# SCH_BMS.net
KiCad netlist of a schematic drawn in Altium Designer
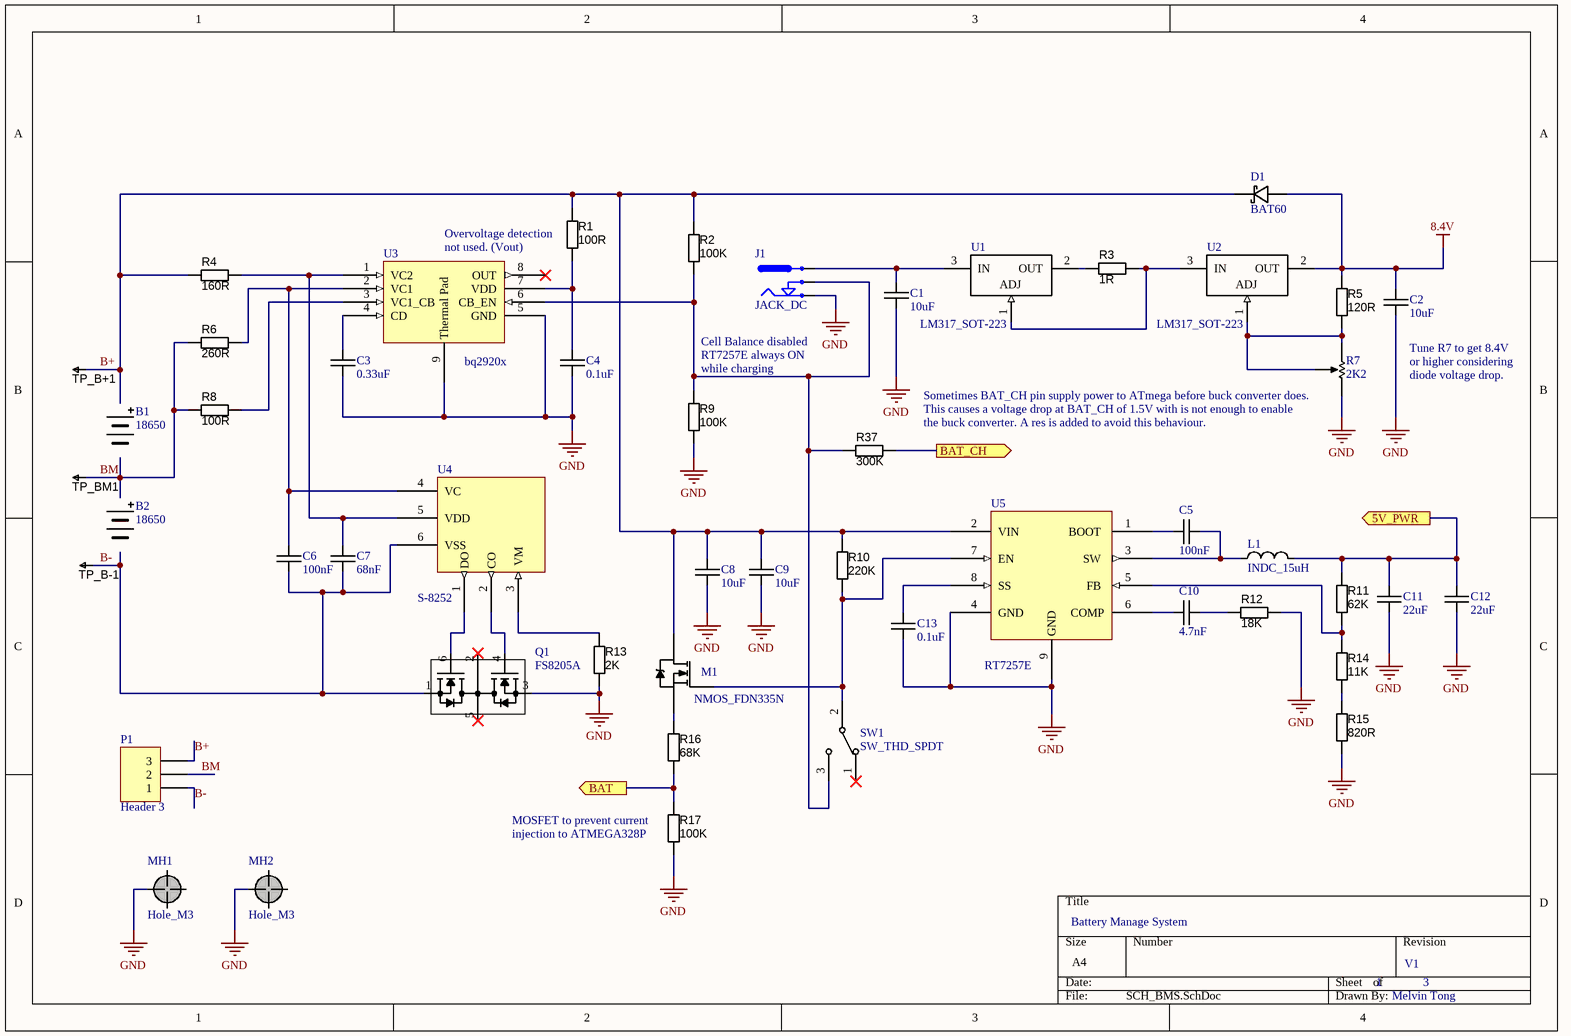
[diagram p0: SCH_BMS.SchDoc]

(export (version "E")
  (design (tool "Eeschema 10.0.6"))
  (components
    (comp (ref "B1") (value "18650") (libsource (lib "Schlib_Sword") (part "Battery_18650")))
    (comp (ref "B2") (value "18650") (libsource (lib "Schlib_Sword") (part "Battery_18650")))
    (comp (ref "C1")
      (value "10uF")
      (footprint "CAP_0805")
      (description "SMD 0805/1206")
      (libsource (lib "Schlib_Sword") (part "CAP_10uF"))
    )
    (comp (ref "C2")
      (value "10uF")
      (footprint "CAP_1206")
      (description "SMD 0805/1206")
      (libsource (lib "Schlib_Sword") (part "CAP_10uF"))
    )
    (comp (ref "C3")
      (value "0.33uF")
      (footprint "CAP_0805")
      (description "SMD 0805")
      (libsource (lib "Schlib_Sword") (part "CAP_330nF"))
    )
    (comp (ref "C4")
      (value "0.1uF")
      (footprint "CAP_0805")
      (description "SMD 0805")
      (libsource (lib "Schlib_Sword") (part "CAP_0.1uF"))
    )
    (comp (ref "C5")
      (value "100nF")
      (footprint "CAP_0805")
      (description "SMD 0805")
      (libsource (lib "Schlib_Sword") (part "CAP_100nF"))
    )
    (comp (ref "C6")
      (value "100nF")
      (footprint "CAP_0805")
      (description "SMD 0805")
      (libsource (lib "Schlib_Sword") (part "CAP_0.1uF"))
    )
    (comp (ref "C7")
      (value "68nF")
      (footprint "CAP_0805")
      (description "SMD 0805")
      (libsource (lib "Schlib_Sword") (part "CAP_0.1uF"))
    )
    (comp (ref "C8")
      (value "10uF")
      (footprint "CAP_1206")
      (description "SMD 0805/1206")
      (libsource (lib "Schlib_Sword") (part "CAP_10uF"))
    )
    (comp (ref "C9")
      (value "10uF")
      (footprint "CAP_1206")
      (description "SMD 0805/1206")
      (libsource (lib "Schlib_Sword") (part "CAP_10uF"))
    )
    (comp (ref "C10")
      (value "4.7nF")
      (footprint "CAP_0805")
      (description "SMD 0805")
      (libsource (lib "Schlib_Sword") (part "CAP_4.7nF"))
    )
    (comp (ref "C11")
      (value "22uF")
      (footprint "CAP_1206")
      (description "SMD 1206")
      (libsource (lib "Schlib_Sword") (part "CAP_22uF"))
    )
    (comp (ref "C12")
      (value "22uF")
      (footprint "CAP_1206")
      (description "SMD 1206")
      (libsource (lib "Schlib_Sword") (part "CAP_22uF"))
    )
    (comp (ref "C13")
      (value "0.1uF")
      (footprint "CAP_0805")
      (description "SMD 0805")
      (libsource (lib "Schlib_Sword") (part "CAP_0.1uF"))
    )
    (comp (ref "D1")
      (value "BAT60")
      (footprint "SOD323")
      (description "Schottky Diode 3A, Vf~0.24V, Vr=10V")
      (libsource (lib "Schlib_Sword") (part "BAT60"))
    )
    (comp (ref "J1") (value "JACK_DC") (footprint "DC-004") (libsource (lib "Schlib_Sword") (part "JACK_DC")))
    (comp (ref "L1")
      (value "INDC_15uH")
      (footprint "IND_15uH")
      (description "15uH ±20% 4.2A 28.4mΩ SMD,12.5x12.5x6.5mm Power Inductors")
      (libsource (lib "Schlib_Sword") (part "INDC_15uH"))
    )
    (comp (ref "M1")
      (value "NMOS_FDN335N")
      (footprint "SOT23_213")
      (libsource (lib "Schlib_Sword") (part "NMOS_FDN335N"))
    )
    (comp (ref "MH1")
      (value "Hole_M3")
      (footprint "Hole_M3")
      (libsource (lib "Schlib_Sword") (part "Hole_M3"))
    )
    (comp (ref "MH2")
      (value "Hole_M3")
      (footprint "Hole_M3")
      (libsource (lib "Schlib_Sword") (part "Hole_M3"))
    )
    (comp (ref "P1")
      (value "Header 3")
      (footprint "HDR1X3")
      (description "Header, 3-Pin")
      (fields (field (name "PUBLISHER") "Altium Limited"))
      (libsource (lib "Miscellaneous Connectors") (part "Header 3"))
    )
    (comp (ref "Q1")
      (value "FS8205A")
      (footprint "SOT23-6")
      (description "NMOS, Drain-Connected, Imax 6A")
      (libsource (lib "Schlib_Sword") (part "FS8205A"))
    )
    (comp (ref "R1")
      (value "100R")
      (footprint "RESC3216X70N")
      (description "Resistor SMD, 1206")
      (libsource (lib "") (part "RES_100R_1"))
    )
    (comp (ref "R2")
      (value "100K")
      (footprint "RESC3216X70N")
      (description "Resistor SMD, 1206")
      (libsource (lib "Schlib_Sword") (part "RES_100K"))
    )
    (comp (ref "R3")
      (value "1R")
      (footprint "RESC6332X70N")
      (description "Resistor SMD 1Ω ±5% 2W ±400ppm/℃ 2512")
      (fields (field (name "TOLERANCE") "±5%") (field (name "Comment") "RES_1R_2512"))
      (libsource (lib "Schlib_Sword") (part "RES_1R_2512"))
    )
    (comp (ref "R4")
      (value "160R")
      (footprint "RESC3216X70N")
      (description "Resistor SMD, 1206")
      (libsource (lib "Schlib_Sword") (part "RES_160R"))
    )
    (comp (ref "R5")
      (value "120R")
      (footprint "RESC3216X70N")
      (description "Resistor SMD, 1206")
      (libsource (lib "Schlib_Sword") (part "RES_120R"))
    )
    (comp (ref "R6")
      (value "260R")
      (footprint "RESC3216X70N")
      (description "Resistor SMD, 1206")
      (libsource (lib "Schlib_Sword") (part "RES_260R"))
    )
    (comp (ref "R7")
      (value "2K2")
      (footprint "RES_VAR")
      (description "Resistor SMD Variable")
      (libsource (lib "Schlib_Sword") (part "RES_Var_2K2"))
    )
    (comp (ref "R8")
      (value "100R")
      (footprint "RESC3216X70N")
      (description "Resistor SMD, 1206")
      (libsource (lib "Schlib_Sword") (part "RES_100R"))
    )
    (comp (ref "R9")
      (value "100K")
      (footprint "RESC3216X70N")
      (description "Resistor SMD, 1206")
      (libsource (lib "Schlib_Sword") (part "RES_100K"))
    )
    (comp (ref "R10")
      (value "220K")
      (footprint "RESC3216X70N")
      (description "Resistor SMD, 1206")
      (libsource (lib "Schlib_Sword") (part "RES_220K"))
    )
    (comp (ref "R11")
      (value "62K")
      (footprint "RESC3216X70N")
      (description "Resistor SMD, 1206")
      (libsource (lib "Schlib_Sword") (part "RES_62K"))
    )
    (comp (ref "R12")
      (value "18K")
      (footprint "RESC3216X70N")
      (description "Resistor SMD, 1206")
      (libsource (lib "Schlib_Sword") (part "RES_18K"))
    )
    (comp (ref "R13")
      (value "2K")
      (footprint "RESC3216X70N")
      (description "Resistor SMD, 1206")
      (libsource (lib "Schlib_Sword") (part "RES_2K"))
    )
    (comp (ref "R14")
      (value "11K")
      (footprint "RESC3216X70N")
      (description "Resistor SMD, 1206")
      (libsource (lib "Schlib_Sword") (part "RES_11K"))
    )
    (comp (ref "R15")
      (value "820R")
      (footprint "RESC3216X70N")
      (description "Resistor SMD, 1206")
      (libsource (lib "Schlib_Sword") (part "RES_820R"))
    )
    (comp (ref "R16")
      (value "68K")
      (footprint "RESC3216X70N")
      (description "Resistor SMD, 1206")
      (libsource (lib "Schlib_Sword") (part "RES_68K"))
    )
    (comp (ref "R17")
      (value "100K")
      (footprint "RESC3216X70N")
      (description "Resistor SMD, 1206")
      (libsource (lib "") (part "RES_100K_1"))
    )
    (comp (ref "R37")
      (value "300K")
      (footprint "RESC3216X70N")
      (description "Resistor SMD, 1206")
      (libsource (lib "Schlib_Sword") (part "RES_300K"))
    )
    (comp (ref "SW1")
      (value "SW_THD_SPDT")
      (footprint "3P_header")
      (description "Switch 2 position")
      (libsource (lib "Schlib_Sword") (part "SW_THD_SPDT"))
    )
    (comp (ref "TP_B+1")
      (value "TESTPOINT")
      (footprint "TP-R20")
      (description "SMD test pin")
      (libsource (lib "Schlib_Sword") (part "TESTPOINT"))
    )
    (comp (ref "TP_B-1")
      (value "TESTPOINT")
      (footprint "TP-R20")
      (description "SMD test pin")
      (libsource (lib "Schlib_Sword") (part "TESTPOINT"))
    )
    (comp (ref "TP_BM1")
      (value "TESTPOINT")
      (footprint "TP-R20")
      (description "SMD test pin")
      (libsource (lib "Schlib_Sword") (part "TESTPOINT"))
    )
    (comp (ref "U1")
      (value "LM317_SOT-223")
      (footprint "SOT223")
      (description "Linear Voltage Regulator")
      (libsource (lib "Schlib_Sword") (part "LM317_SOT-223"))
    )
    (comp (ref "U2")
      (value "LM317_SOT-223")
      (footprint "SOT223")
      (description "Linear Voltage Regulator")
      (libsource (lib "Schlib_Sword") (part "LM317_SOT-223"))
    )
    (comp (ref "U3")
      (value "bq2920x")
      (footprint "bq2920x")
      (description "Automatic Cell Balance 2S Li-Ion Battery")
      (libsource (lib "Schlib_Sword") (part "bq2920x"))
    )
    (comp (ref "U4")
      (value "S-8252")
      (footprint "SOT23-6")
      (description "Battery protection IC for 2S battery pack")
      (libsource (lib "Schlib_Sword") (part "S-8252"))
    )
    (comp (ref "U5")
      (value "RT7257E")
      (footprint "RT7257E")
      (description "DC/DC Buck Converter, 3A, 4.5V-17V Vin")
      (libsource (lib "Schlib_Sword") (part "RT7257E"))
    )
  )
  (nets
    (net (code "1") (name "/5V_PWR") (class "Default")
      (node (ref "C11") (pin "1") (pintype "passive"))
      (node (ref "C12") (pin "1") (pintype "passive"))
      (node (ref "L1") (pin "2") (pinfunction "2_2") (pintype "passive"))
      (node (ref "R11") (pin "1") (pinfunction "1_1") (pintype "passive"))
    )
    (net (code "2") (name "/B+") (class "Default")
      (node (ref "C8") (pin "1") (pintype "passive"))
      (node (ref "C9") (pin "1") (pintype "passive"))
      (node (ref "D1") (pin "K") (pinfunction "K_K") (pintype "passive"))
      (node (ref "M1") (pin "3") (pinfunction "D_3") (pintype "passive"))
      (node (ref "P1") (pin "3") (pinfunction "3_3") (pintype "passive"))
      (node (ref "R1") (pin "2") (pinfunction "2_2") (pintype "passive"))
      (node (ref "R10") (pin "1") (pinfunction "1_1") (pintype "passive"))
      (node (ref "R2") (pin "2") (pinfunction "2_2") (pintype "passive"))
      (node (ref "R4") (pin "1") (pinfunction "1_1") (pintype "passive"))
      (node (ref "TP_B+1") (pin "1") (pintype "passive"))
      (node (ref "U5") (pin "2") (pinfunction "VIN_2") (pintype "power_in"))
    )
    (net (code "3") (name "/B-") (class "Default")
      (node (ref "C6") (pin "2") (pintype "passive"))
      (node (ref "C7") (pin "2") (pintype "passive"))
      (node (ref "P1") (pin "1") (pinfunction "1_1") (pintype "passive"))
      (node (ref "Q1") (pin "1") (pinfunction "S1_1") (pintype "passive"))
      (node (ref "TP_B-1") (pin "1") (pintype "passive"))
      (node (ref "U4") (pin "6") (pinfunction "VSS_6") (pintype "power_in"))
    )
    (net (code "4") (name "/BAT") (class "Default")
      (node (ref "R16") (pin "2") (pinfunction "2_2") (pintype "passive"))
      (node (ref "R17") (pin "1") (pinfunction "1_1") (pintype "passive"))
    )
    (net (code "5") (name "/BAT_CH") (class "Default")
      (node (ref "R37") (pin "2") (pinfunction "2_2") (pintype "passive"))
    )
    (net (code "6") (name "/BM") (class "Default")
      (node (ref "P1") (pin "2") (pinfunction "2_2") (pintype "passive"))
      (node (ref "R6") (pin "1") (pinfunction "1_1") (pintype "passive"))
      (node (ref "R8") (pin "1") (pinfunction "1_1") (pintype "passive"))
      (node (ref "TP_BM1") (pin "1") (pintype "passive"))
    )
    (net (code "7") (name "8.4V") (class "Default")
      (node (ref "C2") (pin "1") (pintype "passive"))
      (node (ref "D1") (pin "A") (pinfunction "A_A") (pintype "passive"))
      (node (ref "R5") (pin "1") (pinfunction "1_1") (pintype "passive"))
      (node (ref "U2") (pin "2") (pinfunction "OUT_2") (pintype "power_in"))
    )
    (net (code "8") (name "GND") (class "Default")
      (node (ref "C1") (pin "2") (pintype "passive"))
      (node (ref "C11") (pin "2") (pintype "passive"))
      (node (ref "C12") (pin "2") (pintype "passive"))
      (node (ref "C13") (pin "2") (pintype "passive"))
      (node (ref "C2") (pin "2") (pintype "passive"))
      (node (ref "C3") (pin "2") (pintype "passive"))
      (node (ref "C4") (pin "2") (pintype "passive"))
      (node (ref "C8") (pin "2") (pintype "passive"))
      (node (ref "C9") (pin "2") (pintype "passive"))
      (node (ref "J1") (pin "1") (pinfunction "1_1") (pintype "passive"))
      (node (ref "MH1") (pin "MH") (pinfunction "MH_MH") (pintype "passive"))
      (node (ref "MH2") (pin "MH") (pinfunction "MH_MH") (pintype "passive"))
      (node (ref "Q1") (pin "3") (pinfunction "D2_3") (pintype "passive"))
      (node (ref "R12") (pin "2") (pinfunction "2_2") (pintype "passive"))
      (node (ref "R13") (pin "2") (pinfunction "2_2") (pintype "passive"))
      (node (ref "R15") (pin "2") (pinfunction "2_2") (pintype "passive"))
      (node (ref "R17") (pin "2") (pinfunction "2_2") (pintype "passive"))
      (node (ref "R7") (pin "3") (pinfunction "CW_3") (pintype "passive"))
      (node (ref "R9") (pin "1") (pinfunction "1_1") (pintype "passive"))
      (node (ref "U3") (pin "5") (pinfunction "GND_5") (pintype "power_in"))
      (node (ref "U3") (pin "9") (pinfunction "Thermal_Pad_9") (pintype "power_in"))
      (node (ref "U5") (pin "4") (pinfunction "GND_4") (pintype "power_in"))
      (node (ref "U5") (pin "9") (pinfunction "GND_9") (pintype "power_in"))
    )
    (net (code "9") (name "Net-(C10-Pad2)") (class "Default")
      (node (ref "C10") (pin "2") (pintype "passive"))
      (node (ref "R12") (pin "1") (pinfunction "1_1") (pintype "passive"))
    )
    (net (code "10") (name "Net-(M1-G)") (class "Default")
      (node (ref "M1") (pin "1") (pinfunction "G_1") (pintype "passive"))
      (node (ref "R10") (pin "2") (pinfunction "2_2") (pintype "passive"))
      (node (ref "SW1") (pin "2") (pinfunction "2_2") (pintype "passive"))
      (node (ref "U5") (pin "7") (pinfunction "EN_7") (pintype "input"))
    )
    (net (code "11") (name "Net-(M1-S)") (class "Default")
      (node (ref "M1") (pin "2") (pinfunction "S_2") (pintype "passive"))
      (node (ref "R16") (pin "1") (pinfunction "1_1") (pintype "passive"))
    )
    (net (code "12") (name "Net-(Q1-G1)") (class "Default")
      (node (ref "Q1") (pin "6") (pinfunction "G1_6") (pintype "passive"))
      (node (ref "U4") (pin "1") (pinfunction "DO_1") (pintype "output"))
    )
    (net (code "13") (name "Net-(Q1-G2)") (class "Default")
      (node (ref "Q1") (pin "4") (pinfunction "G2_4") (pintype "passive"))
      (node (ref "U4") (pin "2") (pinfunction "CO_2") (pintype "output"))
    )
    (net (code "14") (name "Net-(R7-CCW)") (class "Default")
      (node (ref "R5") (pin "2") (pinfunction "2_2") (pintype "passive"))
      (node (ref "R7") (pin "1") (pinfunction "CCW_1") (pintype "passive"))
      (node (ref "R7") (pin "2") (pinfunction "WIPER_2") (pintype "passive"))
      (node (ref "U2") (pin "1") (pinfunction "ADJ_1") (pintype "input"))
    )
    (net (code "15") (name "Net-(R14-Pad2)") (class "Default")
      (node (ref "R14") (pin "2") (pinfunction "2_2") (pintype "passive"))
      (node (ref "R15") (pin "1") (pinfunction "1_1") (pintype "passive"))
    )
    (net (code "16") (name "Net-(U1-ADJ)") (class "Default")
      (node (ref "R3") (pin "2") (pinfunction "2_2") (pintype "passive"))
      (node (ref "U1") (pin "1") (pinfunction "ADJ_1") (pintype "input"))
      (node (ref "U2") (pin "3") (pinfunction "IN_3") (pintype "power_in"))
    )
    (net (code "17") (name "Net-(U1-IN)") (class "Default")
      (node (ref "C1") (pin "1") (pintype "passive"))
      (node (ref "J1") (pin "2") (pinfunction "2_2") (pintype "passive"))
      (node (ref "U1") (pin "3") (pinfunction "IN_3") (pintype "power_in"))
    )
    (net (code "18") (name "Net-(U1-OUT)") (class "Default")
      (node (ref "R3") (pin "1") (pinfunction "1_1") (pintype "passive"))
      (node (ref "U1") (pin "2") (pinfunction "OUT_2") (pintype "power_in"))
    )
    (net (code "19") (name "Net-(U3-CB_EN)") (class "Default")
      (node (ref "J1") (pin "3") (pinfunction "3_3") (pintype "passive"))
      (node (ref "R2") (pin "1") (pinfunction "1_1") (pintype "passive"))
      (node (ref "R37") (pin "1") (pinfunction "1_1") (pintype "passive"))
      (node (ref "R9") (pin "2") (pinfunction "2_2") (pintype "passive"))
      (node (ref "SW1") (pin "3") (pinfunction "3_3") (pintype "passive"))
      (node (ref "U3") (pin "6") (pinfunction "CB_EN_6") (pintype "input"))
    )
    (net (code "20") (name "Net-(U3-CD)") (class "Default")
      (node (ref "C3") (pin "1") (pintype "passive"))
      (node (ref "U3") (pin "4") (pinfunction "CD_4") (pintype "input"))
    )
    (net (code "21") (name "Net-(U3-VC1)") (class "Default")
      (node (ref "C6") (pin "1") (pintype "passive"))
      (node (ref "R6") (pin "2") (pinfunction "2_2") (pintype "passive"))
      (node (ref "U3") (pin "2") (pinfunction "VC1_2") (pintype "input"))
      (node (ref "U4") (pin "4") (pinfunction "VC_4") (pintype "power_in"))
    )
    (net (code "22") (name "Net-(U3-VC1_CB)") (class "Default")
      (node (ref "R8") (pin "2") (pinfunction "2_2") (pintype "passive"))
      (node (ref "U3") (pin "3") (pinfunction "VC1_CB_3") (pintype "input"))
    )
    (net (code "23") (name "Net-(U3-VC2)") (class "Default")
      (node (ref "C7") (pin "1") (pintype "passive"))
      (node (ref "R4") (pin "2") (pinfunction "2_2") (pintype "passive"))
      (node (ref "U3") (pin "1") (pinfunction "VC2_1") (pintype "input"))
      (node (ref "U4") (pin "5") (pinfunction "VDD_5") (pintype "power_in"))
    )
    (net (code "24") (name "Net-(U3-VDD)") (class "Default")
      (node (ref "C4") (pin "1") (pintype "passive"))
      (node (ref "R1") (pin "1") (pinfunction "1_1") (pintype "passive"))
      (node (ref "U3") (pin "7") (pinfunction "VDD_7") (pintype "power_in"))
    )
    (net (code "25") (name "Net-(U4-_VM)") (class "Default")
      (node (ref "R13") (pin "1") (pinfunction "1_1") (pintype "passive"))
      (node (ref "U4") (pin "3") (pinfunction "_VM_3") (pintype "input"))
    )
    (net (code "26") (name "Net-(U5-BOOT)") (class "Default")
      (node (ref "C5") (pin "1") (pintype "passive"))
      (node (ref "U5") (pin "1") (pinfunction "BOOT_1") (pintype "passive"))
    )
    (net (code "27") (name "Net-(U5-COMP)") (class "Default")
      (node (ref "C10") (pin "1") (pintype "passive"))
      (node (ref "U5") (pin "6") (pinfunction "COMP_6") (pintype "passive"))
    )
    (net (code "28") (name "Net-(U5-FB)") (class "Default")
      (node (ref "R11") (pin "2") (pinfunction "2_2") (pintype "passive"))
      (node (ref "R14") (pin "1") (pinfunction "1_1") (pintype "passive"))
      (node (ref "U5") (pin "5") (pinfunction "FB_5") (pintype "input"))
    )
    (net (code "29") (name "Net-(U5-SS)") (class "Default")
      (node (ref "C13") (pin "1") (pintype "passive"))
      (node (ref "U5") (pin "8") (pinfunction "SS_8") (pintype "input"))
    )
    (net (code "30") (name "Net-(U5-SW)") (class "Default")
      (node (ref "C5") (pin "2") (pintype "passive"))
      (node (ref "L1") (pin "1") (pinfunction "1_1") (pintype "passive"))
      (node (ref "U5") (pin "3") (pinfunction "SW_3") (pintype "output"))
    )
    (net (code "31") (name "unconnected-(Q1-D1-Pad2)") (class "Default")
      (node (ref "Q1") (pin "2") (pinfunction "D1_2") (pintype "passive+no_connect"))
    )
    (net (code "32") (name "unconnected-(Q1-D2-Pad5)") (class "Default")
      (node (ref "Q1") (pin "5") (pinfunction "D2_5") (pintype "passive+no_connect"))
    )
    (net (code "33") (name "unconnected-(SW1-Pad1)") (class "Default")
      (node (ref "SW1") (pin "1") (pinfunction "1_1") (pintype "passive+no_connect"))
    )
    (net (code "34") (name "unconnected-(U3-OUT-Pad8)") (class "Default")
      (node (ref "U3") (pin "8") (pinfunction "OUT_8") (pintype "output+no_connect"))
    )
  )
)
